# TCAN1146_PINOUT.net
KiCad netlist of a schematic drawn in Altium Designer
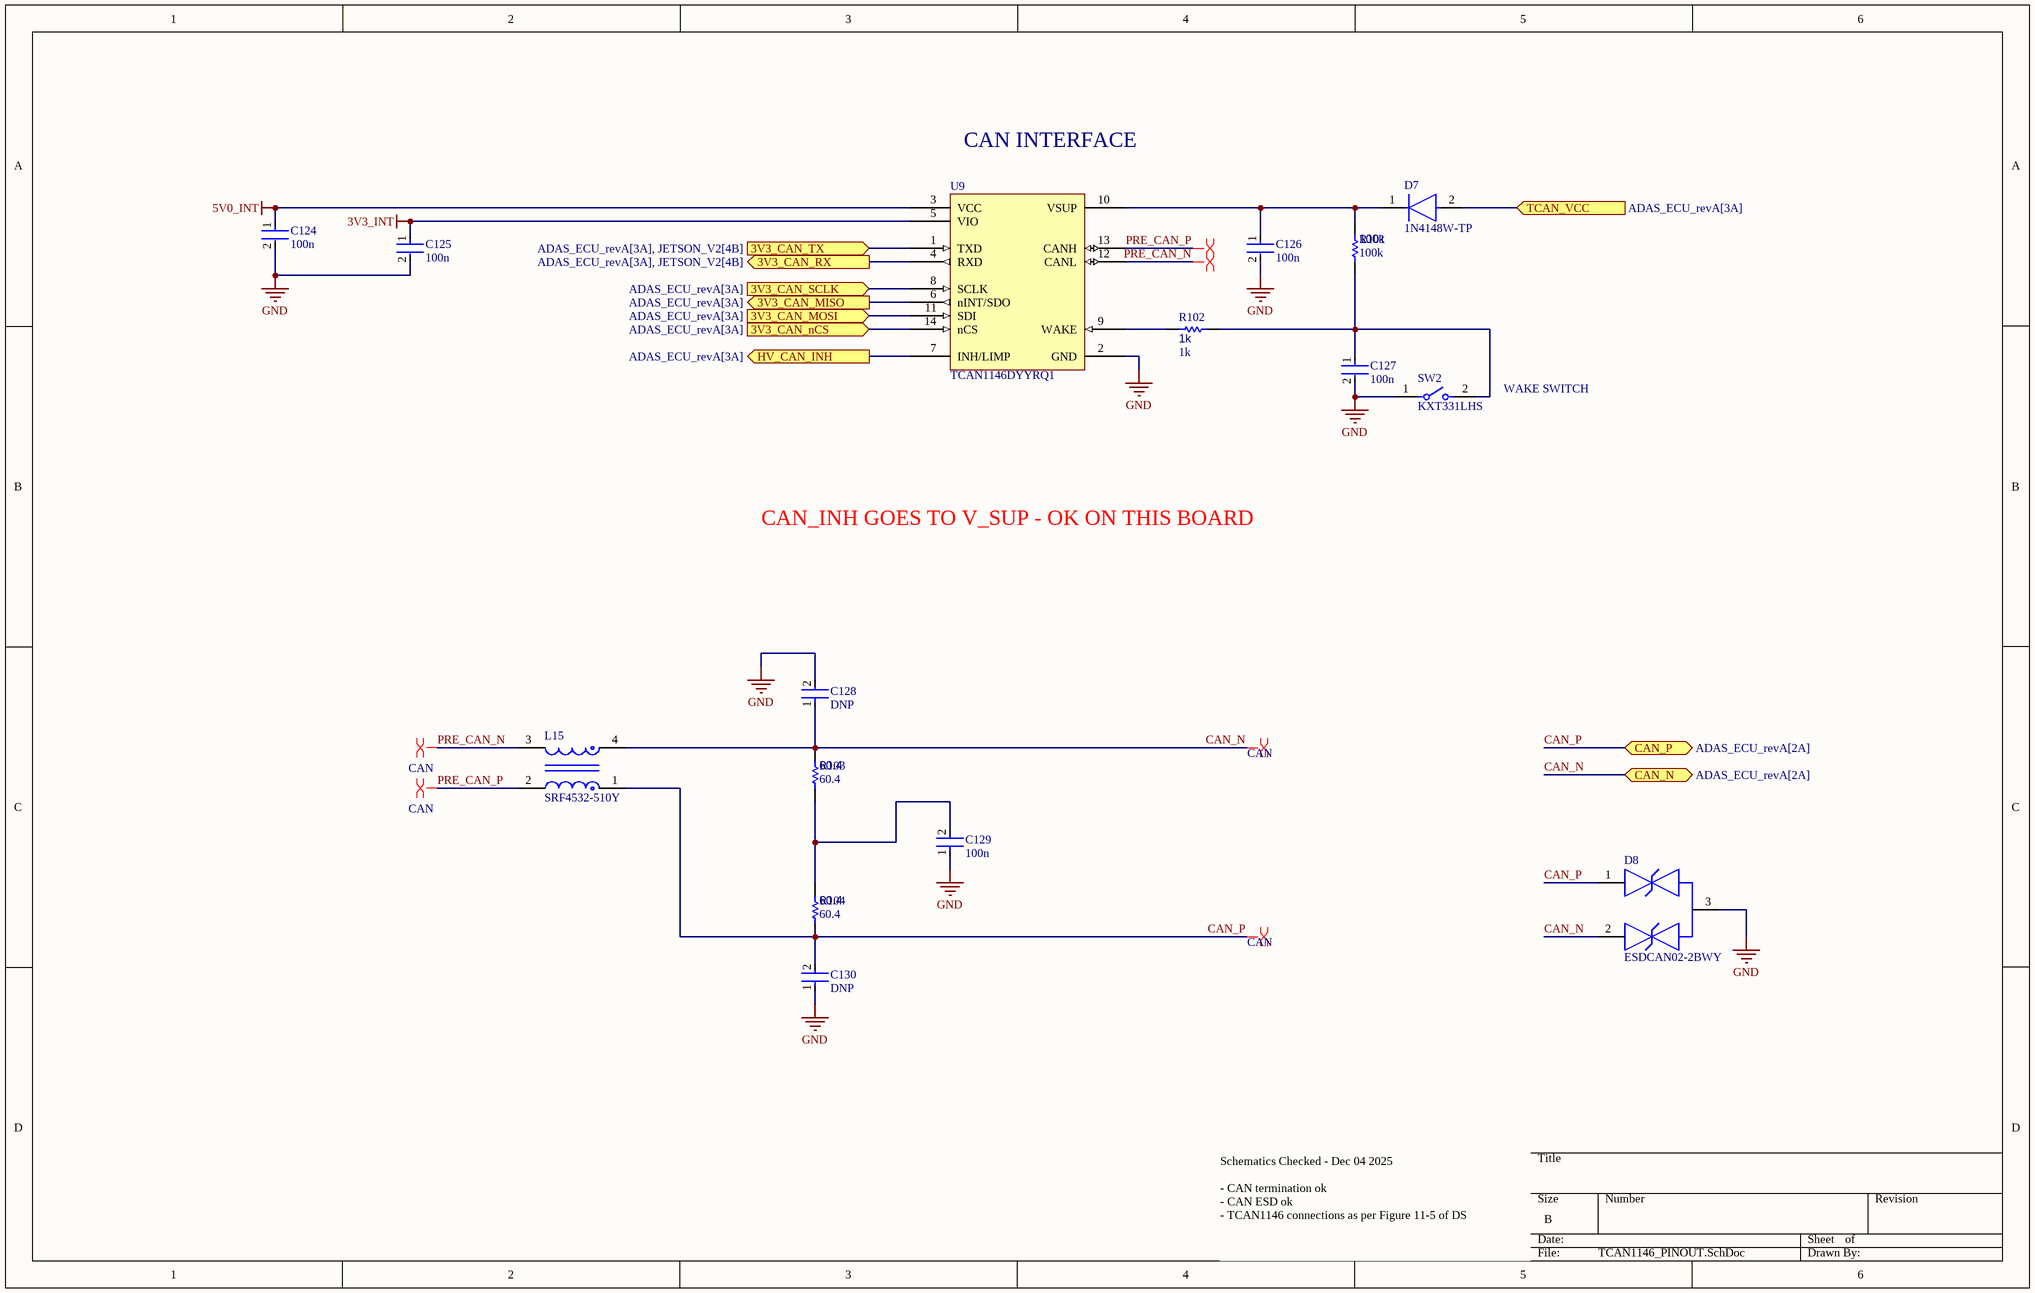
[diagram p0: TCAN1146_PINOUT.SchDoc]

(export (version "E")
  (design (tool "Eeschema 10.0.6"))
  (components
    (comp (ref "C124")
      (value "100n")
      (footprint "FP-0402-L_1_0_0_05-W_0_5-IPC_A")
      (description "LARGE PADS, 0402 CAP, CHANGE COMMENT TO MATCH REAL P/N")
      (libsource (lib "Space Concordia") (part "b4654b650e69147ec39a6b967a45e02"))
    )
    (comp (ref "C125")
      (value "100n")
      (footprint "FP-0402-L_1_0_0_05-W_0_5-IPC_A")
      (description "LARGE PADS, 0402 CAP, CHANGE COMMENT TO MATCH REAL P/N")
      (libsource (lib "Space Concordia") (part "b4654b650e69147ec39a6b967a45e02"))
    )
    (comp (ref "C126")
      (value "100n")
      (footprint "FP-0402-L_1_0_0_05-W_0_5-IPC_A")
      (description "LARGE PADS, 0402 CAP, CHANGE COMMENT TO MATCH REAL P/N")
      (libsource (lib "Space Concordia") (part "b4654b650e69147ec39a6b967a45e02"))
    )
    (comp (ref "C127")
      (value "100n")
      (footprint "FP-0402-L_1_0_0_05-W_0_5-IPC_A")
      (description "LARGE PADS, 0402 CAP, CHANGE COMMENT TO MATCH REAL P/N")
      (libsource (lib "Space Concordia") (part "b4654b650e69147ec39a6b967a45e02"))
    )
    (comp (ref "C128")
      (value "DNP")
      (footprint "FP-0402-L_1_0_0_05-W_0_5-IPC_A")
      (description "LARGE PADS, 0402 CAP, CHANGE COMMENT TO MATCH REAL P/N")
      (libsource (lib "Space Concordia") (part "b4654b650e69147ec39a6b967a45e02"))
    )
    (comp (ref "C129")
      (value "100n")
      (footprint "FP-0402-L_1_0_0_05-W_0_5-IPC_A")
      (description "LARGE PADS, 0402 CAP, CHANGE COMMENT TO MATCH REAL P/N")
      (libsource (lib "Space Concordia") (part "b4654b650e69147ec39a6b967a45e02"))
    )
    (comp (ref "C130")
      (value "DNP")
      (footprint "FP-0402-L_1_0_0_05-W_0_5-IPC_A")
      (description "LARGE PADS, 0402 CAP, CHANGE COMMENT TO MATCH REAL P/N")
      (libsource (lib "Space Concordia") (part "b4654b650e69147ec39a6b967a45e02"))
    )
    (comp (ref "D7")
      (value "1N4148W-TP")
      (footprint "FP-SOD-123-IPC_A")
      (description "DIODE GEN PURP 100V 150MA SOD123")
      (libsource (lib "Altium Content Vault") (part "d7152d700b627762746794eb795d46e"))
    )
    (comp (ref "D8")
      (value "ESDCAN02-2BWY")
      (footprint "FP-SOT323-3L-MFG")
      (description "TVS DIODE 26.5V 44V SOT323-3")
      (fields
        (field (name "MANUFACTURER") "STMicroelectronics")
        (field (name "OCTOPART") "https://octopart.com/esdcan02-2bwy-stmicroelectronics-58631133")
      )
      (libsource (lib "Altium Content Vault") (part "0b9019fb5e52ed66df21ec1535be59d"))
    )
    (comp (ref "L15")
      (value "SRF4532-510Y")
      (footprint "FP-SRF4532-MFG")
      (description "CMC 51UH 200MA 2LN 2KOHM SMD")
      (fields (field (name "TOLERANCE") "50%"))
      (libsource (lib "Altium Content Vault") (part "aca3f6a10b859f211cca95010157f3b"))
    )
    (comp (ref "R101")
      (value "100k")
      (footprint "R0603B")
      (description "Resistor")
      (fields (field (name "ALTIUM_VALUE") "100k"))
      (libsource (lib "Space Concordia") (part "Resistor"))
    )
    (comp (ref "R102")
      (value "1k")
      (footprint "R0603B")
      (description "Resistor")
      (fields (field (name "ALTIUM_VALUE") "1k"))
      (libsource (lib "Space Concordia") (part "Resistor"))
    )
    (comp (ref "R103")
      (value "60.4")
      (footprint "R0603B")
      (description "Resistor")
      (fields (field (name "ALTIUM_VALUE") "60.4"))
      (libsource (lib "Space Concordia") (part "Resistor"))
    )
    (comp (ref "R104")
      (value "60.4")
      (footprint "R0603B")
      (description "Resistor")
      (fields (field (name "ALTIUM_VALUE") "60.4"))
      (libsource (lib "Space Concordia") (part "Resistor"))
    )
    (comp (ref "SW2")
      (value "KXT331LHS")
      (footprint "FP-KXT331LHS-MFG")
      (description "SWITCH TACTILE SPST-NO 0.02A 15V")
      (libsource (lib "Altium Content Vault") (part "bb27bde45df87f1f469753f287ef5ae"))
    )
    (comp (ref "U9")
      (value "TCAN1146DYYRQ1")
      (footprint "TCAN1146DYYRQ1-Footprint-1")
      (libsource (lib "Space Concordia") (part "CMP-015-00012-2"))
    )
  )
  (nets
    (net (code "1") (name "/3V3_CAN_MISO") (class "Default")
      (node (ref "U9") (pin "6") (pinfunction "nINT/SDO_6") (pintype "output"))
    )
    (net (code "2") (name "/3V3_CAN_MOSI") (class "Default")
      (node (ref "U9") (pin "11") (pinfunction "SDI_11") (pintype "input"))
    )
    (net (code "3") (name "/3V3_CAN_RX") (class "Default")
      (node (ref "U9") (pin "4") (pinfunction "RXD_4") (pintype "output"))
    )
    (net (code "4") (name "/3V3_CAN_SCLK") (class "Default")
      (node (ref "U9") (pin "8") (pinfunction "SCLK_8") (pintype "input"))
    )
    (net (code "5") (name "/3V3_CAN_TX") (class "Default")
      (node (ref "U9") (pin "1") (pinfunction "TXD_1") (pintype "input"))
    )
    (net (code "6") (name "/3V3_CAN_nCS") (class "Default")
      (node (ref "U9") (pin "14") (pinfunction "nCS_14") (pintype "input"))
    )
    (net (code "7") (name "/CAN_N") (class "Default")
      (node (ref "C128") (pin "1") (pinfunction "1_1") (pintype "passive"))
      (node (ref "D8") (pin "2") (pinfunction "2_2") (pintype "passive"))
      (node (ref "L15") (pin "4") (pinfunction "4_4") (pintype "passive"))
      (node (ref "R103") (pin "2") (pinfunction "2_2") (pintype "passive"))
    )
    (net (code "8") (name "/CAN_P") (class "Default")
      (node (ref "C130") (pin "2") (pinfunction "2_2") (pintype "passive"))
      (node (ref "D8") (pin "1") (pinfunction "1_1") (pintype "passive"))
      (node (ref "L15") (pin "1") (pinfunction "1_1") (pintype "passive"))
      (node (ref "R104") (pin "1") (pinfunction "1_1") (pintype "passive"))
    )
    (net (code "9") (name "/HV_CAN_INH") (class "Default")
      (node (ref "U9") (pin "7") (pinfunction "INH/LIMP_7") (pintype "passive"))
    )
    (net (code "10") (name "/PRE_CAN_N") (class "Default")
      (node (ref "L15") (pin "3") (pinfunction "3_3") (pintype "passive"))
      (node (ref "U9") (pin "12") (pinfunction "CANL_12") (pintype "bidirectional"))
    )
    (net (code "11") (name "/PRE_CAN_P") (class "Default")
      (node (ref "L15") (pin "2") (pinfunction "2_2") (pintype "passive"))
      (node (ref "U9") (pin "13") (pinfunction "CANH_13") (pintype "bidirectional"))
    )
    (net (code "12") (name "/TCAN_VCC") (class "Default")
      (node (ref "D7") (pin "2") (pinfunction "A_2") (pintype "passive"))
    )
    (net (code "13") (name "3V3_INT") (class "Default")
      (node (ref "C125") (pin "1") (pinfunction "1_1") (pintype "passive"))
      (node (ref "U9") (pin "5") (pinfunction "VIO_5") (pintype "power_in"))
    )
    (net (code "14") (name "5V0_INT") (class "Default")
      (node (ref "C124") (pin "1") (pinfunction "1_1") (pintype "passive"))
      (node (ref "U9") (pin "3") (pinfunction "VCC_3") (pintype "power_in"))
    )
    (net (code "15") (name "GND") (class "Default")
      (node (ref "C124") (pin "2") (pinfunction "2_2") (pintype "passive"))
      (node (ref "C125") (pin "2") (pinfunction "2_2") (pintype "passive"))
      (node (ref "C126") (pin "2") (pinfunction "2_2") (pintype "passive"))
      (node (ref "C127") (pin "2") (pinfunction "2_2") (pintype "passive"))
      (node (ref "C128") (pin "2") (pinfunction "2_2") (pintype "passive"))
      (node (ref "C129") (pin "1") (pinfunction "1_1") (pintype "passive"))
      (node (ref "C130") (pin "1") (pinfunction "1_1") (pintype "passive"))
      (node (ref "D8") (pin "3") (pinfunction "3_3") (pintype "passive"))
      (node (ref "SW2") (pin "1") (pinfunction "1_1") (pintype "passive"))
      (node (ref "U9") (pin "2") (pinfunction "GND_2") (pintype "power_in"))
    )
    (net (code "16") (name "Net-(C127-Pad1)") (class "Default")
      (node (ref "C127") (pin "1") (pinfunction "1_1") (pintype "passive"))
      (node (ref "R101") (pin "1") (pinfunction "1_1") (pintype "passive"))
      (node (ref "R102") (pin "2") (pinfunction "2_2") (pintype "passive"))
      (node (ref "SW2") (pin "2") (pinfunction "2_2") (pintype "passive"))
    )
    (net (code "17") (name "Net-(C129-Pad2)") (class "Default")
      (node (ref "C129") (pin "2") (pinfunction "2_2") (pintype "passive"))
      (node (ref "R103") (pin "1") (pinfunction "1_1") (pintype "passive"))
      (node (ref "R104") (pin "2") (pinfunction "2_2") (pintype "passive"))
    )
    (net (code "18") (name "Net-(D7-C)") (class "Default")
      (node (ref "C126") (pin "1") (pinfunction "1_1") (pintype "passive"))
      (node (ref "D7") (pin "1") (pinfunction "C_1") (pintype "passive"))
      (node (ref "R101") (pin "2") (pinfunction "2_2") (pintype "passive"))
      (node (ref "U9") (pin "10") (pinfunction "VSUP_10") (pintype "power_in"))
    )
    (net (code "19") (name "Net-(U9-WAKE)") (class "Default")
      (node (ref "R102") (pin "1") (pinfunction "1_1") (pintype "passive"))
      (node (ref "U9") (pin "9") (pinfunction "WAKE_9") (pintype "input"))
    )
  )
)
